# AutoPlantWatering.net
KiCad netlist of a schematic drawn in Altium Designer
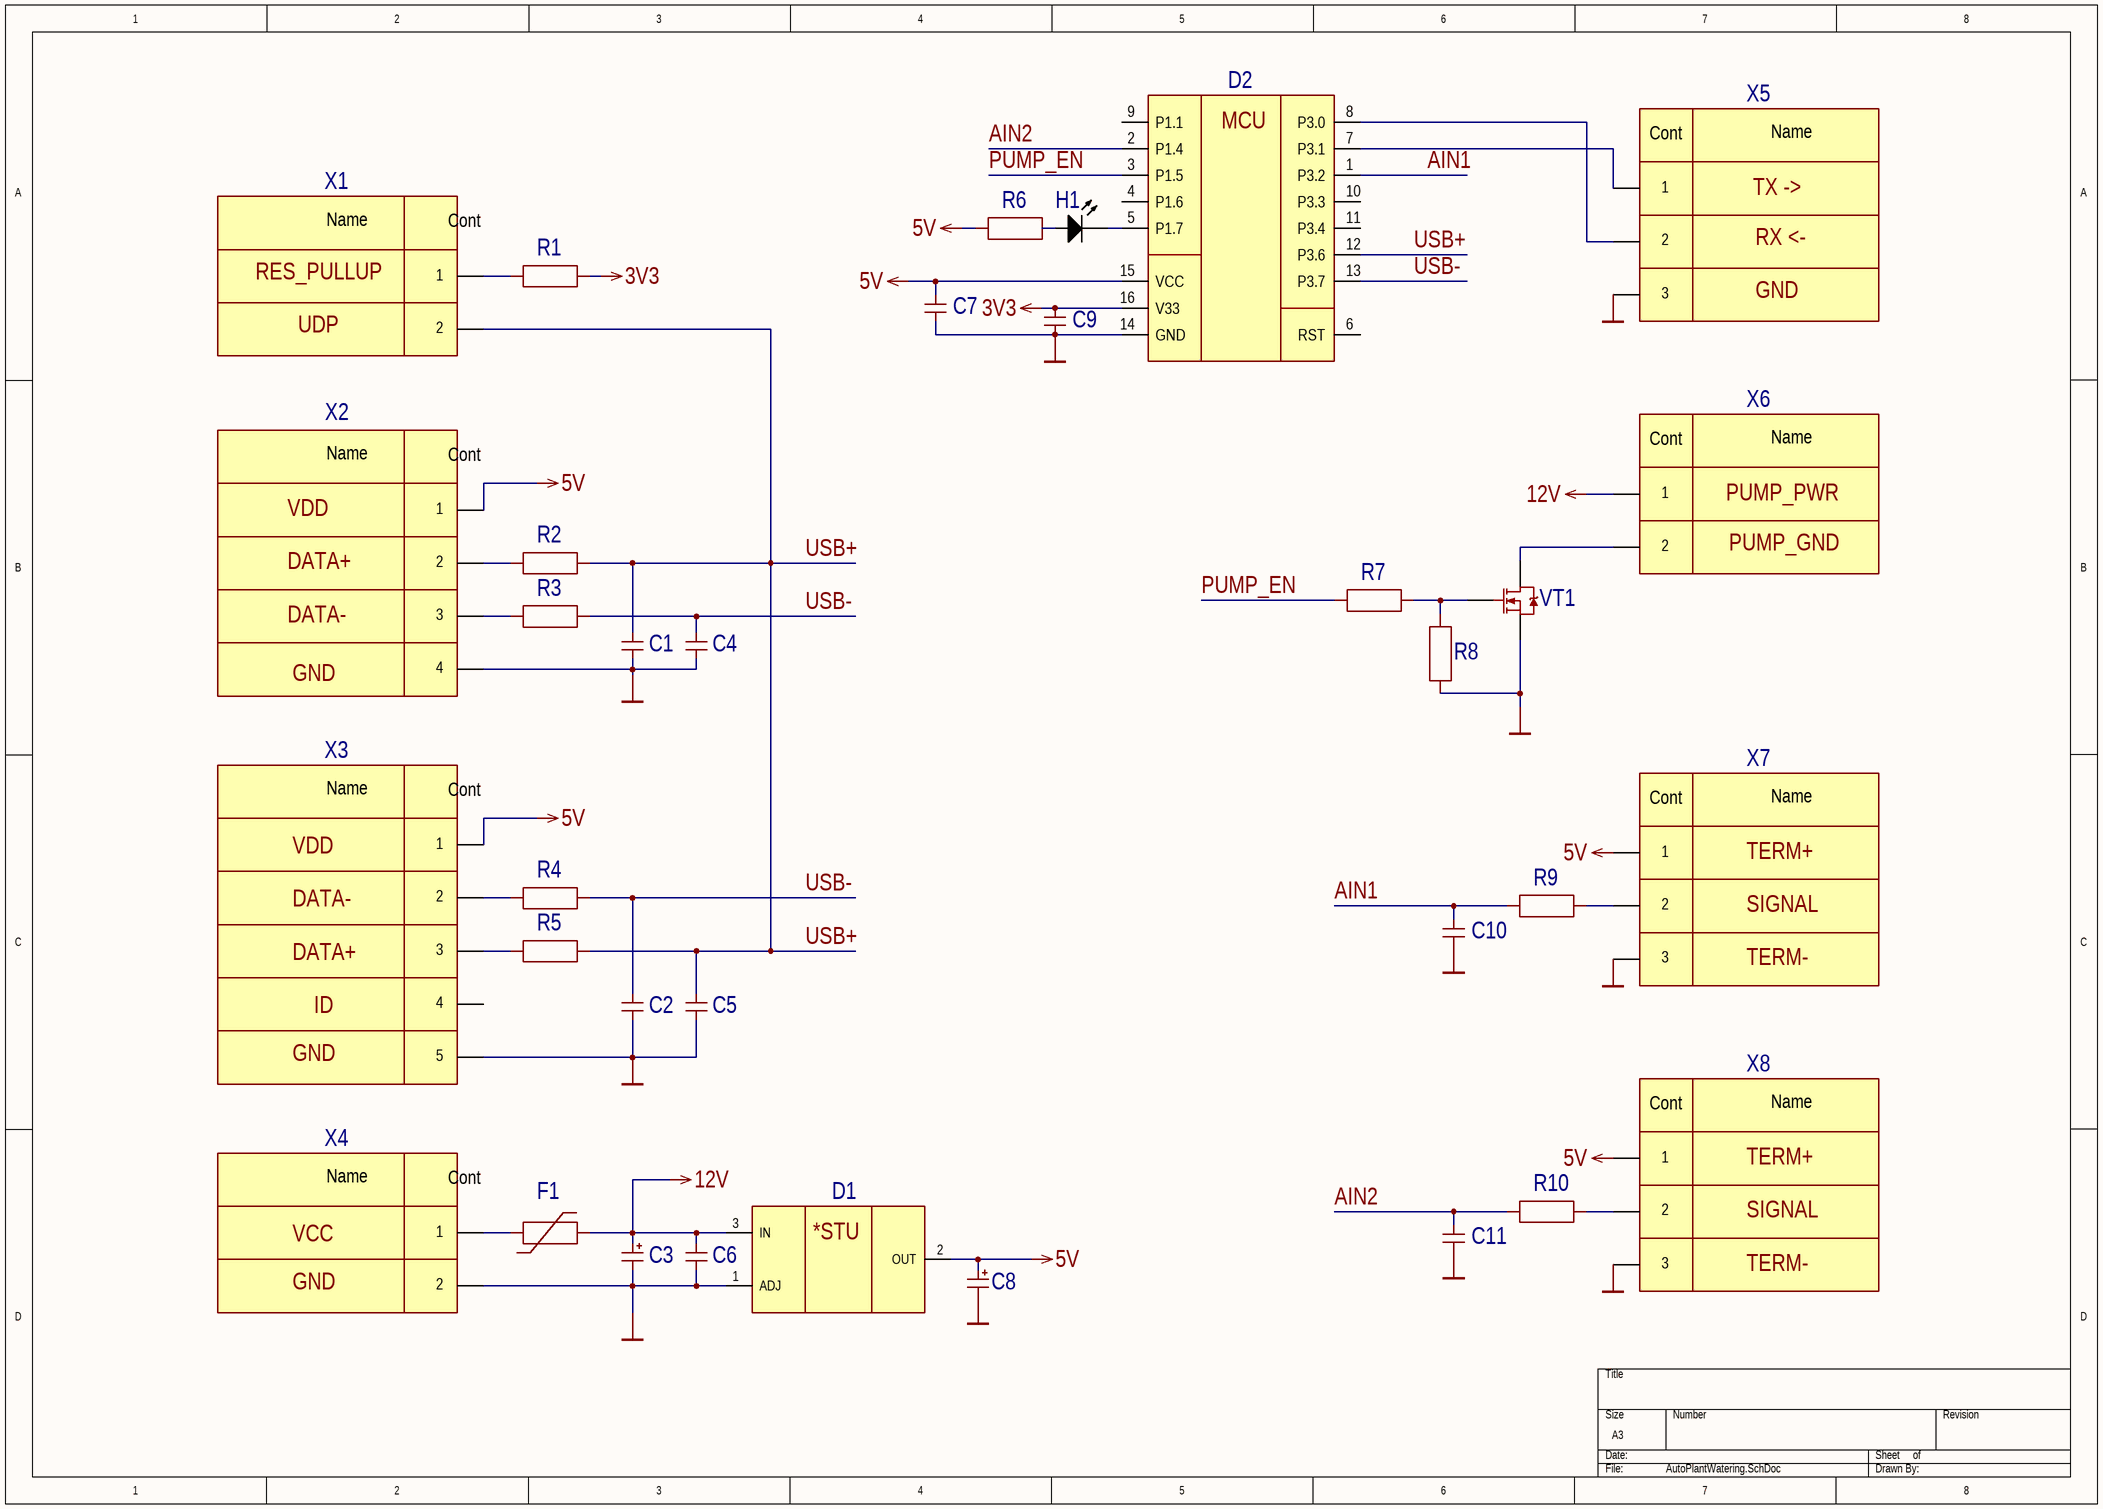
[diagram p0: AutoPlantWatering.SchDoc]

(export (version "E")
  (design (tool "Eeschema 10.0.6"))
  (components
    (comp (ref "C1")
      (value "0805-50 V-COG-47pF±5 %")
      (footprint "SMD-0805C")
      (description "Capacitor")
      (libsource (lib "Passive,Diodes") (part "Cap"))
    )
    (comp (ref "C2")
      (value "0805-50 V-COG-47pF±5 %")
      (footprint "SMD-0805C")
      (description "Capacitor")
      (libsource (lib "Passive,Diodes") (part "Cap"))
    )
    (comp (ref "C3")
      (value "D-20 V-47uF±10 %")
      (footprint "CAP POL 2917/7343")
      (description "Electrolytic capacitor")
      (libsource (lib "Passive,Diodes") (part "Cap_el"))
    )
    (comp (ref "C4")
      (value "0805-50 V-COG-47pF±5 %")
      (footprint "SMD-0805C")
      (description "Capacitor")
      (libsource (lib "Passive,Diodes") (part "Cap"))
    )
    (comp (ref "C5")
      (value "0805-50 V-COG-47pF±5 %")
      (footprint "SMD-0805C")
      (description "Capacitor")
      (libsource (lib "Passive,Diodes") (part "Cap"))
    )
    (comp (ref "C6")
      (value "0805-25 V-X5R-10uF±10 %")
      (footprint "SMD-0805C")
      (description "Capacitor")
      (libsource (lib "Passive,Diodes") (part "Cap"))
    )
    (comp (ref "C7")
      (value "0805-16 V-X7R-0.1uF±10 %")
      (footprint "SMD-0805C")
      (description "Capacitor")
      (libsource (lib "Passive,Diodes") (part "Cap"))
    )
    (comp (ref "C8")
      (value "A-10 V-22uF±10 %")
      (footprint "CAP_TAN_CASE_A")
      (description "Electrolytic capacitor")
      (libsource (lib "Passive,Diodes") (part "Cap_el"))
    )
    (comp (ref "C9")
      (value "0805-16 V-X7R-0.1uF±10 %")
      (footprint "SMD-0805C")
      (description "Capacitor")
      (libsource (lib "Passive,Diodes") (part "Cap"))
    )
    (comp (ref "C10")
      (value "0805-16 V-X7R-0.1uF±10 %")
      (footprint "SMD-0805C")
      (description "Capacitor")
      (libsource (lib "Passive,Diodes") (part "Cap"))
    )
    (comp (ref "C11")
      (value "0805-16 V-X7R-0.1uF±10 %")
      (footprint "SMD-0805C")
      (description "Capacitor")
      (libsource (lib "Passive,Diodes") (part "Cap"))
    )
    (comp (ref "D1")
      (value "AMS1117-5.0")
      (footprint "Devices:SOT223_M")
      (description "3-Terminal Fixed Regulator")
      (fields (field (name "MANUFACTURER") "Advanced Monolithic Systems"))
      (libsource (lib "Devices") (part "LM317"))
    )
    (comp (ref "D2")
      (value "CH552G")
      (footprint "SO-16 _150mil")
      (description "8-bit USB microcontroller")
      (fields (field (name "MANUFACTURER") "WCH"))
      (libsource (lib "Devices") (part "CH55xG"))
    )
    (comp (ref "F1")
      (value "MF-MSMF050")
      (footprint "SMD-1812-FUSE")
      (description "Multifuse")
      (fields (field (name "MANUFACTURER") "Bourns"))
      (libsource (lib "Passive,Diodes") (part "Mulrifuse"))
    )
    (comp (ref "H1")
      (value "GNL-0805GC")
      (footprint "SMD-0805LED")
      (description "Typical INFRARED GaAs LED")
      (fields (field (name "MANUFACTURER") "G-NOR ELECTRONICS"))
      (libsource (lib "Passive,Diodes") (part "LED"))
    )
    (comp (ref "R1")
      (value "0805±5 %-10 kOhm")
      (footprint "SMD-0805-RES")
      (description "Resistor")
      (libsource (lib "Passive,Diodes") (part "Res"))
    )
    (comp (ref "R2")
      (value "0805±5 %-22 Ohm")
      (footprint "SMD-0805-RES")
      (description "Resistor")
      (libsource (lib "Passive,Diodes") (part "Res"))
    )
    (comp (ref "R3")
      (value "0805±5 %-22 Ohm")
      (footprint "SMD-0805-RES")
      (description "Resistor")
      (libsource (lib "Passive,Diodes") (part "Res"))
    )
    (comp (ref "R4")
      (value "0805±5 %-22 Ohm")
      (footprint "SMD-0805-RES")
      (description "Resistor")
      (libsource (lib "Passive,Diodes") (part "Res"))
    )
    (comp (ref "R5")
      (value "0805±5 %-22 Ohm")
      (footprint "SMD-0805-RES")
      (description "Resistor")
      (libsource (lib "Passive,Diodes") (part "Res"))
    )
    (comp (ref "R6")
      (value "0805±5 %-1 kOhm")
      (footprint "SMD-0805-RES")
      (description "Resistor")
      (libsource (lib "") (part "Res_2"))
    )
    (comp (ref "R7")
      (value "0805±5 %-100 Ohm")
      (footprint "SMD-0805-RES")
      (description "Resistor")
      (libsource (lib "Passive,Diodes") (part "Res"))
    )
    (comp (ref "R8")
      (value "0805±5 %-10 kOhm")
      (footprint "SMD-0805-RES")
      (description "Resistor")
      (libsource (lib "") (part "Res_1"))
    )
    (comp (ref "R9")
      (value "0805±5 %-200 Ohm")
      (footprint "SMD-0805-RES")
      (description "Resistor")
      (libsource (lib "Passive,Diodes") (part "Res"))
    )
    (comp (ref "R10")
      (value "0805±5 %-200 Ohm")
      (footprint "SMD-0805-RES")
      (description "Resistor")
      (libsource (lib "Passive,Diodes") (part "Res"))
    )
    (comp (ref "VT1")
      (value "MMBF170LT1G")
      (footprint "SOT23_3")
      (description "N-channel FET")
      (fields (field (name "MANUFACTURER") "ON Semiconductor"))
      (libsource (lib "Passive,Diodes") (part "Transistor_N"))
    )
    (comp (ref "X1")
      (value "DS1022-11*2RD61")
      (footprint "PLS-2_D1")
      (description "Connector PLS-2")
      (fields (field (name "MANUFACTURER") "Connfly Electronic"))
      (libsource (lib "Connectors") (part "PLS-2"))
    )
    (comp (ref "X2")
      (value "DS1021-1*4S61")
      (footprint "PLS-4")
      (description "PLS-4 connector")
      (fields (field (name "MANUFACTURER") "Connfly Electronic"))
      (libsource (lib "Connectors") (part "PLS-4"))
    )
    (comp (ref "X3")
      (value "DS1104-B60SRS")
      (footprint "Mini-USB-B_HOLE")
      (description "Mini USB-B connector")
      (fields (field (name "MANUFACTURER") "Connfly Electronics"))
      (libsource (lib "Connectors") (part "MINI-USB-B"))
    )
    (comp (ref "X4")
      (value "DC-005-5A-2.5-SMT")
      (footprint "PJ_2.5MM_SMT_HOLE")
      (description "Power jack 2.5 mm SMT connector")
      (fields (field (name "MANUFACTURER") "XKB Connectivity"))
      (libsource (lib "Connectors") (part "Power_Jack_SMT_2.5mm"))
    )
    (comp (ref "X5")
      (value "DS1022-11*3RD61")
      (footprint "PLS-3_D1")
      (description "PLS SMD connector")
      (fields (field (name "MANUFACTURER") "Connfly Electronics"))
      (libsource (lib "Connectors") (part "PLS-3"))
    )
    (comp (ref "X6")
      (value "KLS2-125-3.81-02P-4S")
      (footprint "TERM_BLOCK_2")
      (description "Terminal block connector; 2 position")
      (fields (field (name "MANUFACTURER") "KLS"))
      (libsource (lib "Connectors") (part "TERM_BLOCK_2"))
    )
    (comp (ref "X7")
      (value "DS1021-1*3S61")
      (footprint "PLS-3")
      (description "PLS connector")
      (fields (field (name "MANUFACTURER") "Connfly Electronics"))
      (libsource (lib "Connectors") (part "PLS-3"))
    )
    (comp (ref "X8")
      (value "DS1021-1*3S61")
      (footprint "PLS-3")
      (description "PLS connector")
      (fields (field (name "MANUFACTURER") "Connfly Electronics"))
      (libsource (lib "Connectors") (part "PLS-3"))
    )
  )
  (nets
    (net (code "1") (name "/AIN1") (class "Default")
      (node (ref "C10") (pin "2") (pinfunction "2_2") (pintype "passive"))
      (node (ref "D2") (pin "1") (pinfunction "P3.2_1") (pintype "passive"))
      (node (ref "R9") (pin "1") (pinfunction "1_1") (pintype "passive"))
    )
    (net (code "2") (name "/AIN2") (class "Default")
      (node (ref "C11") (pin "2") (pinfunction "2_2") (pintype "passive"))
      (node (ref "D2") (pin "2") (pinfunction "P1.4_2") (pintype "passive"))
      (node (ref "R10") (pin "1") (pinfunction "1_1") (pintype "passive"))
    )
    (net (code "3") (name "/PUMP_EN") (class "Default")
      (node (ref "D2") (pin "3") (pinfunction "P1.5_3") (pintype "passive"))
      (node (ref "R7") (pin "1") (pinfunction "1_1") (pintype "passive"))
    )
    (net (code "4") (name "/USB+") (class "Default")
      (node (ref "C1") (pin "2") (pinfunction "2_2") (pintype "passive"))
      (node (ref "C5") (pin "2") (pinfunction "2_2") (pintype "passive"))
      (node (ref "D2") (pin "12") (pinfunction "P3.6_12") (pintype "passive"))
      (node (ref "R2") (pin "2") (pinfunction "2_2") (pintype "passive"))
      (node (ref "R5") (pin "2") (pinfunction "2_2") (pintype "passive"))
      (node (ref "X1") (pin "2") (pinfunction "2_2") (pintype "passive"))
    )
    (net (code "5") (name "/USB-") (class "Default")
      (node (ref "C2") (pin "2") (pinfunction "2_2") (pintype "passive"))
      (node (ref "C4") (pin "2") (pinfunction "2_2") (pintype "passive"))
      (node (ref "D2") (pin "13") (pinfunction "P3.7_13") (pintype "passive"))
      (node (ref "R3") (pin "2") (pinfunction "2_2") (pintype "passive"))
      (node (ref "R4") (pin "2") (pinfunction "2_2") (pintype "passive"))
    )
    (net (code "6") (name "3V3") (class "Default")
      (node (ref "C9") (pin "2") (pinfunction "2_2") (pintype "passive"))
      (node (ref "D2") (pin "16") (pinfunction "V33_16") (pintype "power_in"))
      (node (ref "R1") (pin "2") (pinfunction "2_2") (pintype "passive"))
    )
    (net (code "7") (name "5V") (class "Default")
      (node (ref "C7") (pin "2") (pinfunction "2_2") (pintype "passive"))
      (node (ref "C8") (pin "1") (pinfunction "1_1") (pintype "passive"))
      (node (ref "D1") (pin "2") (pinfunction "OUT_2") (pintype "power_in"))
      (node (ref "D2") (pin "15") (pinfunction "VCC_15") (pintype "power_in"))
      (node (ref "R6") (pin "2") (pinfunction "2_2") (pintype "passive"))
      (node (ref "X2") (pin "1") (pinfunction "1_1") (pintype "passive"))
      (node (ref "X3") (pin "1") (pinfunction "1_1") (pintype "passive"))
      (node (ref "X7") (pin "1") (pinfunction "1_1") (pintype "passive"))
      (node (ref "X8") (pin "1") (pinfunction "1_1") (pintype "passive"))
    )
    (net (code "8") (name "12V") (class "Default")
      (node (ref "C3") (pin "1") (pinfunction "1_1") (pintype "passive"))
      (node (ref "C6") (pin "2") (pinfunction "2_2") (pintype "passive"))
      (node (ref "D1") (pin "3") (pinfunction "IN_3") (pintype "power_in"))
      (node (ref "F1") (pin "2") (pinfunction "2_2") (pintype "passive"))
      (node (ref "X6") (pin "1") (pinfunction "1_1") (pintype "passive"))
    )
    (net (code "9") (name "GND") (class "Default")
      (node (ref "C1") (pin "1") (pinfunction "1_1") (pintype "passive"))
      (node (ref "C10") (pin "1") (pinfunction "1_1") (pintype "passive"))
      (node (ref "C11") (pin "1") (pinfunction "1_1") (pintype "passive"))
      (node (ref "C2") (pin "1") (pinfunction "1_1") (pintype "passive"))
      (node (ref "C3") (pin "2") (pinfunction "2_2") (pintype "passive"))
      (node (ref "C4") (pin "1") (pinfunction "1_1") (pintype "passive"))
      (node (ref "C5") (pin "1") (pinfunction "1_1") (pintype "passive"))
      (node (ref "C6") (pin "1") (pinfunction "1_1") (pintype "passive"))
      (node (ref "C7") (pin "1") (pinfunction "1_1") (pintype "passive"))
      (node (ref "C8") (pin "2") (pinfunction "2_2") (pintype "passive"))
      (node (ref "C9") (pin "1") (pinfunction "1_1") (pintype "passive"))
      (node (ref "D1") (pin "1") (pinfunction "ADJ_1") (pintype "passive"))
      (node (ref "D2") (pin "14") (pinfunction "GND_14") (pintype "power_in"))
      (node (ref "R8") (pin "1") (pinfunction "1_1") (pintype "passive"))
      (node (ref "VT1") (pin "2") (pinfunction "S_2") (pintype "passive"))
      (node (ref "X2") (pin "4") (pinfunction "4_4") (pintype "passive"))
      (node (ref "X3") (pin "5") (pinfunction "5_5") (pintype "passive"))
      (node (ref "X4") (pin "2") (pinfunction "2_2") (pintype "passive"))
      (node (ref "X5") (pin "3") (pinfunction "3_3") (pintype "passive"))
      (node (ref "X7") (pin "3") (pinfunction "3_3") (pintype "passive"))
      (node (ref "X8") (pin "3") (pinfunction "3_3") (pintype "passive"))
    )
    (net (code "10") (name "Net-(D2-P1.7)") (class "Default")
      (node (ref "D2") (pin "5") (pinfunction "P1.7_5") (pintype "passive"))
      (node (ref "H1") (pin "2") (pinfunction "K_2") (pintype "passive"))
    )
    (net (code "11") (name "Net-(D2-P3.0)") (class "Default")
      (node (ref "D2") (pin "8") (pinfunction "P3.0_8") (pintype "passive"))
      (node (ref "X5") (pin "2") (pinfunction "2_2") (pintype "passive"))
    )
    (net (code "12") (name "Net-(D2-P3.1)") (class "Default")
      (node (ref "D2") (pin "7") (pinfunction "P3.1_7") (pintype "passive"))
      (node (ref "X5") (pin "1") (pinfunction "1_1") (pintype "passive"))
    )
    (net (code "13") (name "Net-(F1-Pad1)") (class "Default")
      (node (ref "F1") (pin "1") (pinfunction "1_1") (pintype "passive"))
      (node (ref "X4") (pin "1") (pinfunction "1_1") (pintype "passive"))
    )
    (net (code "14") (name "Net-(H1-A)") (class "Default")
      (node (ref "H1") (pin "1") (pinfunction "A_1") (pintype "passive"))
      (node (ref "R6") (pin "1") (pinfunction "1_1") (pintype "passive"))
    )
    (net (code "15") (name "Net-(R1-Pad1)") (class "Default")
      (node (ref "R1") (pin "1") (pinfunction "1_1") (pintype "passive"))
      (node (ref "X1") (pin "1") (pinfunction "1_1") (pintype "passive"))
    )
    (net (code "16") (name "Net-(R2-Pad1)") (class "Default")
      (node (ref "R2") (pin "1") (pinfunction "1_1") (pintype "passive"))
      (node (ref "X2") (pin "2") (pinfunction "2_2") (pintype "passive"))
    )
    (net (code "17") (name "Net-(R3-Pad1)") (class "Default")
      (node (ref "R3") (pin "1") (pinfunction "1_1") (pintype "passive"))
      (node (ref "X2") (pin "3") (pinfunction "3_3") (pintype "passive"))
    )
    (net (code "18") (name "Net-(R4-Pad1)") (class "Default")
      (node (ref "R4") (pin "1") (pinfunction "1_1") (pintype "passive"))
      (node (ref "X3") (pin "2") (pinfunction "2_2") (pintype "passive"))
    )
    (net (code "19") (name "Net-(R5-Pad1)") (class "Default")
      (node (ref "R5") (pin "1") (pinfunction "1_1") (pintype "passive"))
      (node (ref "X3") (pin "3") (pinfunction "3_3") (pintype "passive"))
    )
    (net (code "20") (name "Net-(R9-Pad2)") (class "Default")
      (node (ref "R9") (pin "2") (pinfunction "2_2") (pintype "passive"))
      (node (ref "X7") (pin "2") (pinfunction "2_2") (pintype "passive"))
    )
    (net (code "21") (name "Net-(R10-Pad2)") (class "Default")
      (node (ref "R10") (pin "2") (pinfunction "2_2") (pintype "passive"))
      (node (ref "X8") (pin "2") (pinfunction "2_2") (pintype "passive"))
    )
    (net (code "22") (name "Net-(VT1-D)") (class "Default")
      (node (ref "VT1") (pin "3") (pinfunction "D_3") (pintype "passive"))
      (node (ref "X6") (pin "2") (pinfunction "2_2") (pintype "passive"))
    )
    (net (code "23") (name "Net-(VT1-G)") (class "Default")
      (node (ref "R7") (pin "2") (pinfunction "2_2") (pintype "passive"))
      (node (ref "R8") (pin "2") (pinfunction "2_2") (pintype "passive"))
      (node (ref "VT1") (pin "1") (pinfunction "G_1") (pintype "passive"))
    )
    (net (code "24") (name "unconnected-(D2-P1.1-Pad9)") (class "Default")
      (node (ref "D2") (pin "9") (pinfunction "P1.1_9") (pintype "passive"))
    )
    (net (code "25") (name "unconnected-(D2-P1.6-Pad4)") (class "Default")
      (node (ref "D2") (pin "4") (pinfunction "P1.6_4") (pintype "passive"))
    )
    (net (code "26") (name "unconnected-(D2-P3.3-Pad10)") (class "Default")
      (node (ref "D2") (pin "10") (pinfunction "P3.3_10") (pintype "passive"))
    )
    (net (code "27") (name "unconnected-(D2-P3.4-Pad11)") (class "Default")
      (node (ref "D2") (pin "11") (pinfunction "P3.4_11") (pintype "passive"))
    )
    (net (code "28") (name "unconnected-(D2-RST-Pad6)") (class "Default")
      (node (ref "D2") (pin "6") (pinfunction "RST_6") (pintype "passive"))
    )
    (net (code "29") (name "unconnected-(X3-Pad4)") (class "Default")
      (node (ref "X3") (pin "4") (pinfunction "4_4") (pintype "passive"))
    )
  )
)
